# bleeding_edge-full_control.net
KiCad netlist of a schematic drawn in EasyEDA
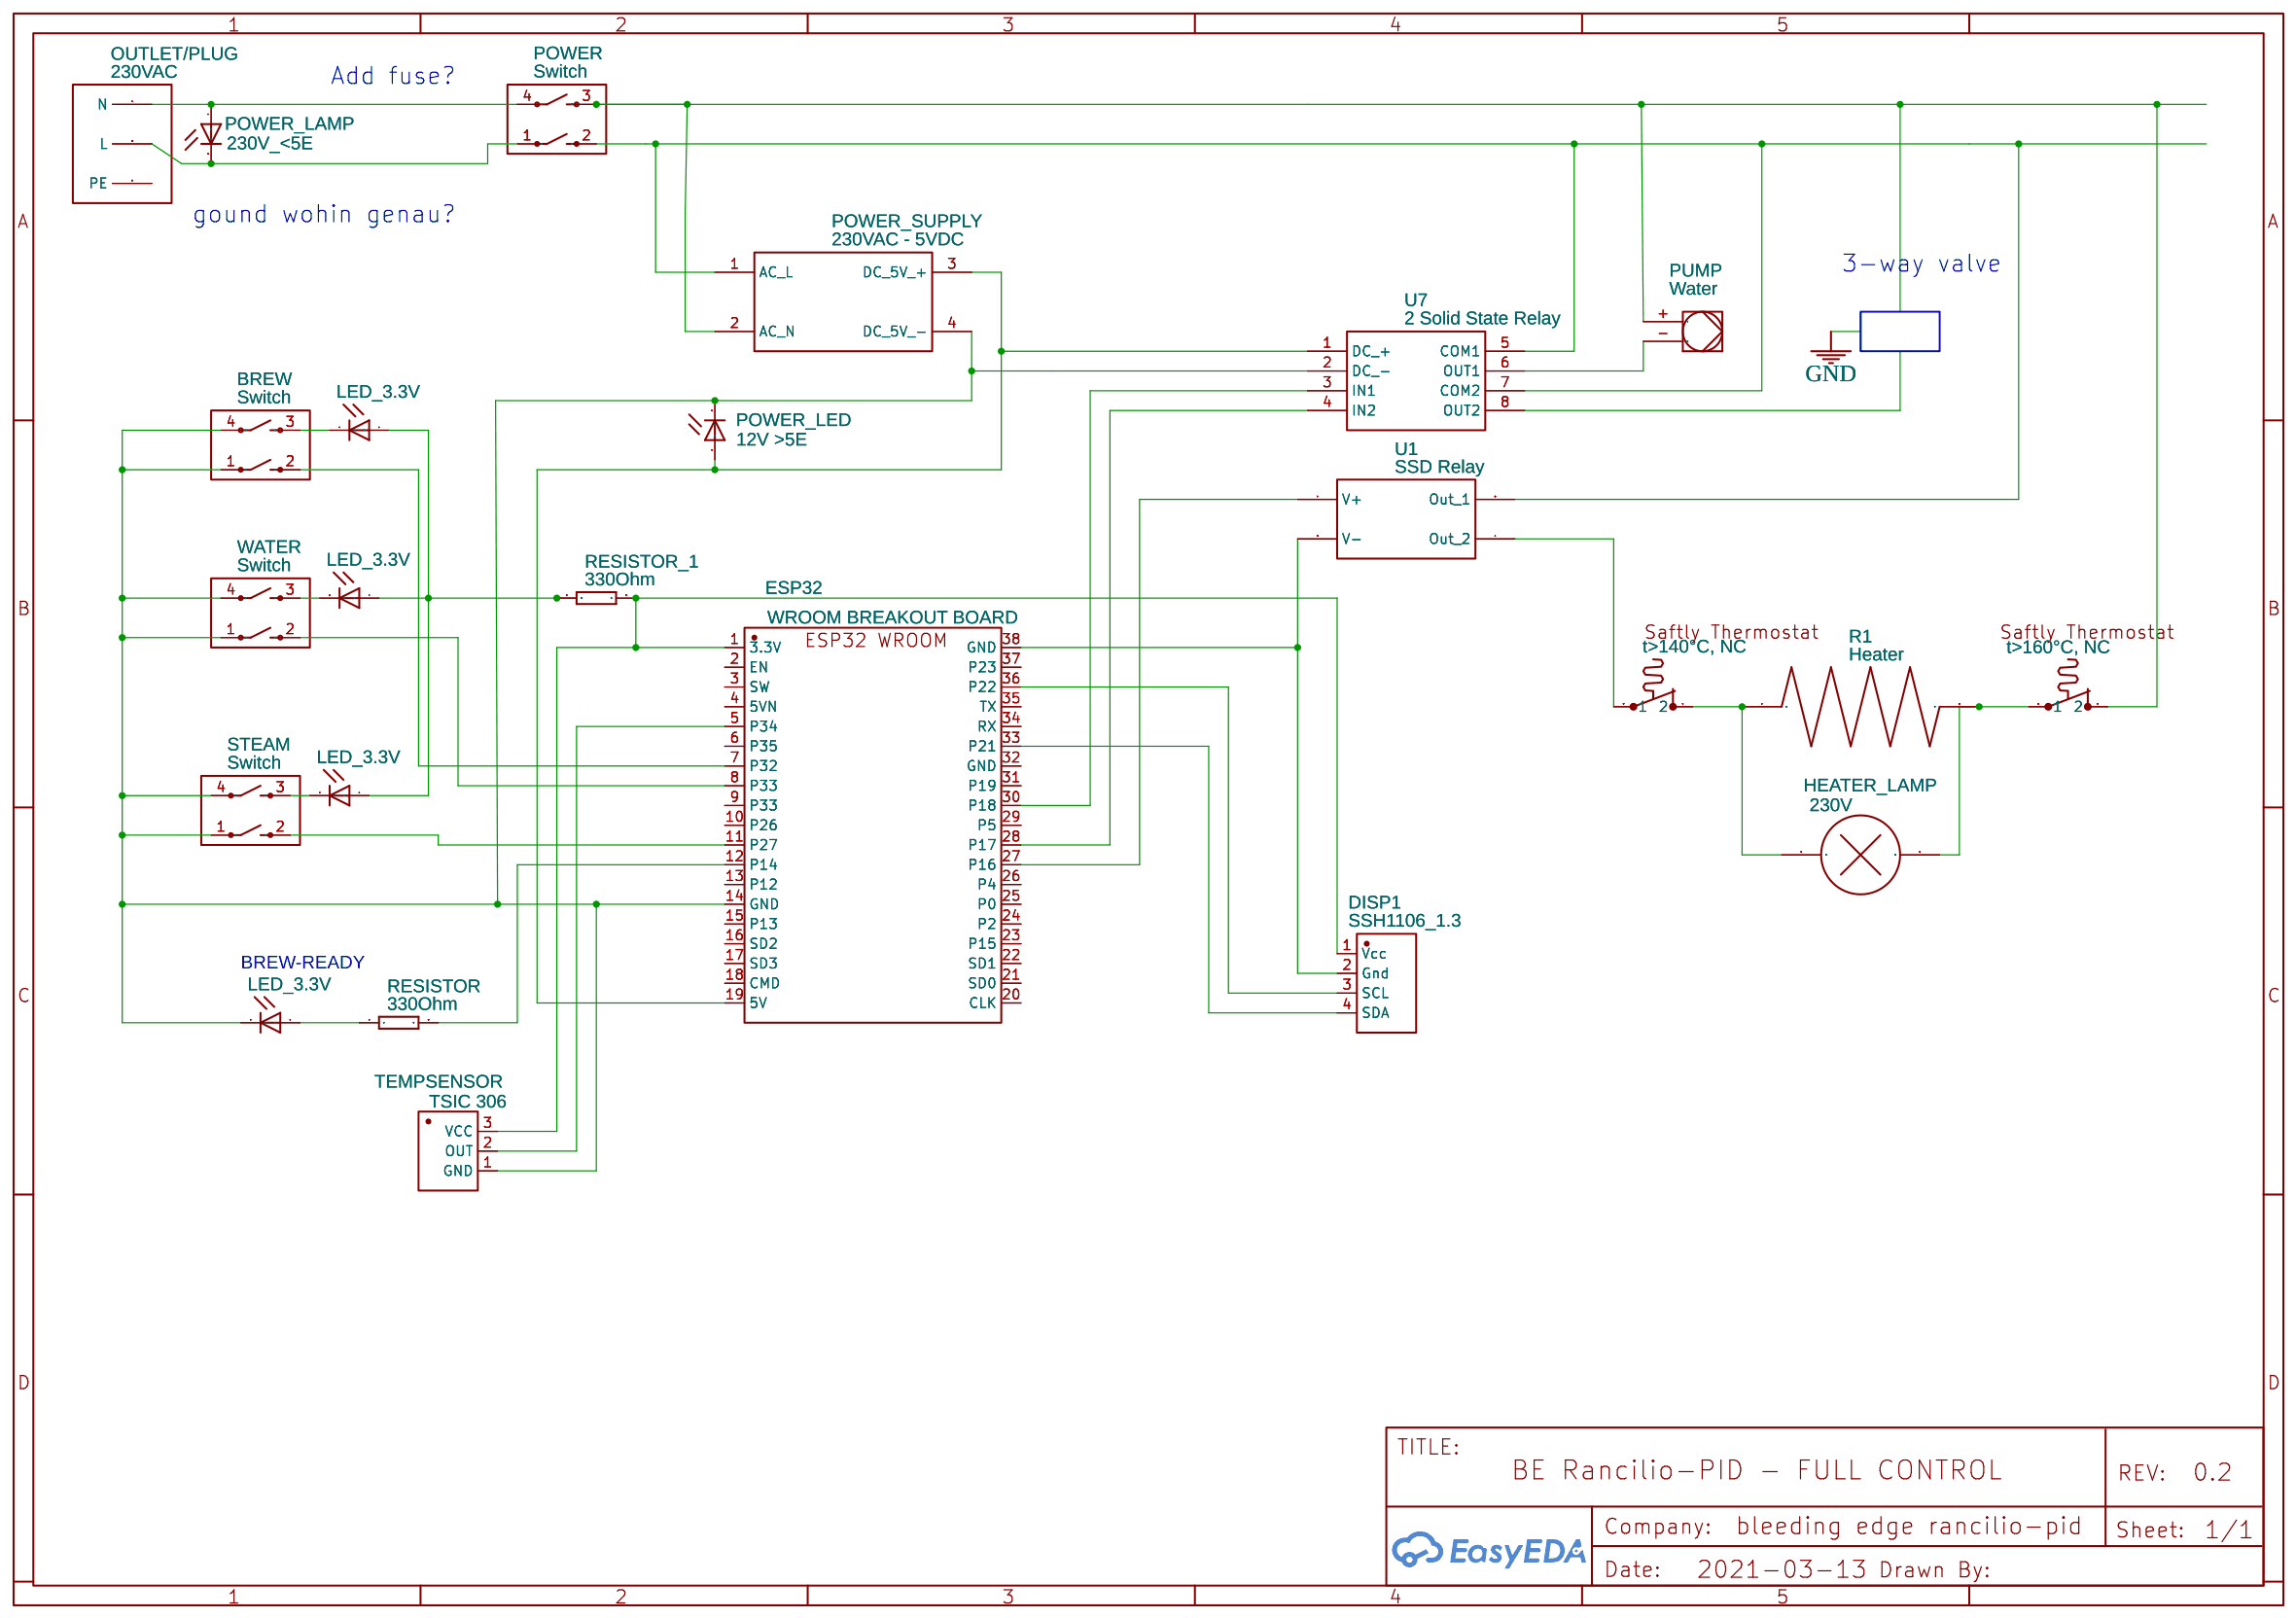
[diagram p0: schematic sheet]

(export (version "E")
  (design (tool "Eeschema 10.0.6"))
  (components
    (comp (ref "BREW")
      (value "Switch")
      (fields
        (field (name "BOM_Manufacturer Part") "Rancilio Switch")
        (field (name "BOM_Supplier Part") "C14121")
      )
      (libsource (lib "") (part "Rancilio Switch_1"))
    )
    (comp (ref "DISP1")
      (value "SSH1106_1.3")
      (fields (field (name "BOM_Manufacturer Part") "Tribium"))
      (libsource (lib "") (part "SSH1106_1.3"))
    )
    (comp (ref "ESP32")
      (value "WROOM BREAKOUT BOARD")
      (libsource (lib "") (part "ESP32 WROOM BREAKOUT BOARD"))
    )
    (comp (ref "HEATER_LAMP")
      (value "230V")
      (fields (field (name "BOM_Manufacturer Part") "Light"))
      (libsource (lib "") (part "Light"))
    )
    (comp (ref "LED1") (value "LED_3.3V") (libsource (lib "") (part "LED")))
    (comp (ref "LED2") (value "LED_3.3V") (libsource (lib "") (part "LED")))
    (comp (ref "LED3") (value "LED_3.3V") (libsource (lib "") (part "LED")))
    (comp (ref "LED4") (value "LED_3.3V") (libsource (lib "") (part "LED")))
    (comp (ref "OUTLET/PLUG")
      (value "230VAC")
      (fields (field (name "BOM_Supplier Part") "undefined"))
      (libsource (lib "") (part "230VAC OUTLET/PLUG"))
    )
    (comp (ref "POWER")
      (value "Switch")
      (fields
        (field (name "BOM_Manufacturer Part") "Rancilio Switch")
        (field (name "BOM_Supplier Part") "C14121")
      )
      (libsource (lib "") (part "Rancilio Switch_3"))
    )
    (comp (ref "POWER_LAMP") (value "230V_<5E") (libsource (lib "") (part "LED_2")))
    (comp (ref "POWER_LED") (value "12V >5E") (libsource (lib "") (part "LED_1")))
    (comp (ref "POWER_SUPPLY") (value "230VAC - 5VDC") (libsource (lib "") (part "230VAC - 5VDC")))
    (comp (ref "PUMP") (value "Water") (libsource (lib "") (part "pump")))
    (comp (ref "R1") (value "Heater") (libsource (lib "") (part "Heater")))
    (comp (ref "RESISTOR") (value "330Ohm") (libsource (lib "") (part "RESISTOR_1")))
    (comp (ref "RESISTOR_1") (value "330Ohm") (libsource (lib "") (part "RESISTOR")))
    (comp (ref "STEAM")
      (value "Switch")
      (fields
        (field (name "BOM_Manufacturer Part") "Rancilio Switch")
        (field (name "BOM_Supplier Part") "C14121")
      )
      (libsource (lib "") (part "Rancilio Switch_2"))
    )
    (comp (ref "TEMPSENSOR")
      (value "TSIC 306")
      (fields (field (name "BOM_Manufacturer Part") "Innovative Sensor Technology"))
      (libsource (lib "") (part "TSIC506F"))
    )
    (comp (ref "U1") (value "SSD Relay") (libsource (lib "") (part "SSD Relay")))
    (comp (ref "U6")
      (value "t>140°C, NC")
      (fields (field (name "BOM_Manufacturer Part") "Thermostat"))
      (libsource (lib "") (part "termostat NC_1"))
    )
    (comp (ref "U7") (value "2 Solid State Relay") (libsource (lib "") (part "2 Solid State Relay")))
    (comp (ref "U11")
      (value "t>160°C, NC")
      (fields (field (name "BOM_Manufacturer Part") "Thermostat"))
      (libsource (lib "") (part "termostat NC"))
    )
    (comp (ref "WATER")
      (value "Switch")
      (fields
        (field (name "BOM_Manufacturer Part") "Rancilio Switch")
        (field (name "BOM_Supplier Part") "C14121")
      )
      (libsource (lib "") (part "Rancilio Switch"))
    )
  )
  (nets
    (net (code "2") (name "Net-(DISP1-Gnd)") (class "Default")
      (node (ref "DISP1") (pin "2") (pinfunction "Gnd_2") (pintype "unspecified"))
      (node (ref "ESP32") (pin "38") (pinfunction "GND_38") (pintype "unspecified"))
      (node (ref "U1") (pin "2") (pinfunction "V-_2") (pintype "unspecified"))
    )
    (net (code "3") (name "Net-(DISP1-SCL)") (class "Default")
      (node (ref "DISP1") (pin "3") (pinfunction "SCL_3") (pintype "unspecified"))
      (node (ref "ESP32") (pin "36") (pinfunction "P22_36") (pintype "unspecified"))
    )
    (net (code "4") (name "Net-(DISP1-SDA)") (class "Default")
      (node (ref "DISP1") (pin "4") (pinfunction "SDA_4") (pintype "unspecified"))
      (node (ref "ESP32") (pin "33") (pinfunction "P21_33") (pintype "unspecified"))
    )
    (net (code "5") (name "Net-(DISP1-Vcc)") (class "Default")
      (node (ref "DISP1") (pin "1") (pinfunction "Vcc_1") (pintype "unspecified"))
      (node (ref "ESP32") (pin "1") (pinfunction "3.3V_1") (pintype "unspecified"))
      (node (ref "RESISTOR_1") (pin "2") (pinfunction "2_2") (pintype "unspecified"))
      (node (ref "TEMPSENSOR") (pin "3") (pinfunction "VCC_3") (pintype "unspecified"))
    )
    (net (code "6") (name "Net-(ESP32-5V)") (class "Default")
      (node (ref "ESP32") (pin "19") (pinfunction "5V_19") (pintype "unspecified"))
      (node (ref "POWER_LED") (pin "A") (pinfunction "A_A") (pintype "unspecified"))
      (node (ref "POWER_SUPPLY") (pin "3") (pinfunction "DC_5V_+_3") (pintype "unspecified"))
      (node (ref "U7") (pin "1") (pinfunction "DC_+_1") (pintype "unspecified"))
    )
    (net (code "7") (name "Net-(ESP32-P14)") (class "Default")
      (node (ref "ESP32") (pin "12") (pinfunction "P14_12") (pintype "unspecified"))
      (node (ref "RESISTOR") (pin "2") (pinfunction "2_2") (pintype "unspecified"))
    )
    (net (code "8") (name "Net-(ESP32-P16)") (class "Default")
      (node (ref "ESP32") (pin "27") (pinfunction "P16_27") (pintype "unspecified"))
      (node (ref "U1") (pin "1") (pinfunction "V+_1") (pintype "unspecified"))
    )
    (net (code "9") (name "Net-(ESP32-P17)") (class "Default")
      (node (ref "ESP32") (pin "28") (pinfunction "P17_28") (pintype "unspecified"))
      (node (ref "U7") (pin "4") (pinfunction "IN2_4") (pintype "unspecified"))
    )
    (net (code "10") (name "Net-(ESP32-P18)") (class "Default")
      (node (ref "ESP32") (pin "30") (pinfunction "P18_30") (pintype "unspecified"))
      (node (ref "U7") (pin "3") (pinfunction "IN1_3") (pintype "unspecified"))
    )
    (net (code "11") (name "Net-(ESP32-P27)") (class "Default")
      (node (ref "ESP32") (pin "11") (pinfunction "P27_11") (pintype "unspecified"))
      (node (ref "STEAM") (pin "2") (pinfunction "2_2") (pintype "unspecified"))
    )
    (net (code "12") (name "Net-(ESP32-P32)") (class "Default")
      (node (ref "BREW") (pin "2") (pinfunction "2_2") (pintype "unspecified"))
      (node (ref "ESP32") (pin "7") (pinfunction "P32_7") (pintype "unspecified"))
    )
    (net (code "13") (name "Net-(ESP32-P33-Pad8)") (class "Default")
      (node (ref "ESP32") (pin "8") (pinfunction "P33_8") (pintype "unspecified"))
      (node (ref "WATER") (pin "2") (pinfunction "2_2") (pintype "unspecified"))
    )
    (net (code "14") (name "Net-(ESP32-P34)") (class "Default")
      (node (ref "ESP32") (pin "5") (pinfunction "P34_5") (pintype "unspecified"))
      (node (ref "TEMPSENSOR") (pin "2") (pinfunction "OUT_2") (pintype "unspecified"))
    )
    (net (code "15") (name "Net-(LED1-C)") (class "Default")
      (node (ref "BREW") (pin "1") (pinfunction "1_1") (pintype "unspecified"))
      (node (ref "BREW") (pin "4") (pinfunction "4_4") (pintype "unspecified"))
      (node (ref "ESP32") (pin "14") (pinfunction "GND_14") (pintype "unspecified"))
      (node (ref "LED1") (pin "K") (pinfunction "C_K") (pintype "unspecified"))
      (node (ref "POWER_LED") (pin "K") (pinfunction "C_K") (pintype "unspecified"))
      (node (ref "POWER_SUPPLY") (pin "4") (pinfunction "DC_5V_-_4") (pintype "unspecified"))
      (node (ref "STEAM") (pin "1") (pinfunction "1_1") (pintype "unspecified"))
      (node (ref "STEAM") (pin "4") (pinfunction "4_4") (pintype "unspecified"))
      (node (ref "TEMPSENSOR") (pin "1") (pinfunction "GND_1") (pintype "unspecified"))
      (node (ref "U7") (pin "2") (pinfunction "DC_-_2") (pintype "unspecified"))
      (node (ref "WATER") (pin "1") (pinfunction "1_1") (pintype "unspecified"))
      (node (ref "WATER") (pin "4") (pinfunction "4_4") (pintype "unspecified"))
    )
    (net (code "16") (name "Net-(LED1-PadA)") (class "Default")
      (node (ref "LED1") (pin "A") (pinfunction "A_A") (pintype "unspecified"))
      (node (ref "RESISTOR") (pin "1") (pinfunction "1_1") (pintype "unspecified"))
    )
    (net (code "17") (name "Net-(LED2-C)") (class "Default")
      (node (ref "BREW") (pin "3") (pinfunction "3_3") (pintype "unspecified"))
      (node (ref "LED2") (pin "K") (pinfunction "C_K") (pintype "unspecified"))
    )
    (net (code "18") (name "Net-(LED2-PadA)") (class "Default")
      (node (ref "LED2") (pin "A") (pinfunction "A_A") (pintype "unspecified"))
      (node (ref "LED3") (pin "A") (pinfunction "A_A") (pintype "unspecified"))
      (node (ref "LED4") (pin "A") (pinfunction "A_A") (pintype "unspecified"))
      (node (ref "RESISTOR_1") (pin "1") (pinfunction "1_1") (pintype "unspecified"))
    )
    (net (code "19") (name "Net-(LED3-C)") (class "Default")
      (node (ref "LED3") (pin "K") (pinfunction "C_K") (pintype "unspecified"))
      (node (ref "WATER") (pin "3") (pinfunction "3_3") (pintype "unspecified"))
    )
    (net (code "20") (name "Net-(LED4-C)") (class "Default")
      (node (ref "LED4") (pin "K") (pinfunction "C_K") (pintype "unspecified"))
      (node (ref "STEAM") (pin "3") (pinfunction "3_3") (pintype "unspecified"))
    )
    (net (code "21") (name "Net-(OUTLET/PLUG-L)") (class "Default")
      (node (ref "OUTLET/PLUG") (pin "2") (pinfunction "L_2") (pintype "unspecified"))
      (node (ref "POWER") (pin "1") (pinfunction "1_1") (pintype "unspecified"))
      (node (ref "POWER_LAMP") (pin "K") (pinfunction "C_K") (pintype "unspecified"))
    )
    (net (code "22") (name "Net-(OUTLET/PLUG-N)") (class "Default")
      (node (ref "OUTLET/PLUG") (pin "1") (pinfunction "N_1") (pintype "unspecified"))
      (node (ref "POWER") (pin "4") (pinfunction "4_4") (pintype "unspecified"))
      (node (ref "POWER_LAMP") (pin "A") (pinfunction "A_A") (pintype "unspecified"))
    )
    (net (code "23") (name "Net-(POWER_SUPPLY-AC_L)") (class "Default")
      (node (ref "POWER") (pin "2") (pinfunction "2_2") (pintype "unspecified"))
      (node (ref "POWER_SUPPLY") (pin "1") (pinfunction "AC_L_1") (pintype "unspecified"))
      (node (ref "U1") (pin "3") (pinfunction "Out_1_3") (pintype "unspecified"))
      (node (ref "U7") (pin "5") (pinfunction "COM1_5") (pintype "unspecified"))
      (node (ref "U7") (pin "7") (pinfunction "COM2_7") (pintype "unspecified"))
    )
    (net (code "24") (name "Net-(POWER_SUPPLY-AC_N)") (class "Default")
      (node (ref "POWER") (pin "3") (pinfunction "3_3") (pintype "unspecified"))
      (node (ref "POWER_SUPPLY") (pin "2") (pinfunction "AC_N_2") (pintype "unspecified"))
      (node (ref "PUMP") (pin "+") (pinfunction "1_+") (pintype "unspecified"))
      (node (ref "U11") (pin "1") (pinfunction "2_1") (pintype "unspecified"))
    )
    (net (code "25") (name "Net-(PUMP-2)") (class "Default")
      (node (ref "PUMP") (pin "-") (pinfunction "2_-") (pintype "unspecified"))
      (node (ref "U7") (pin "6") (pinfunction "OUT1_6") (pintype "unspecified"))
    )
    (net (code "26") (name "Net-(U1-Out_2)") (class "Default")
      (node (ref "U1") (pin "4") (pinfunction "Out_2_4") (pintype "unspecified"))
      (node (ref "U6") (pin "2") (pinfunction "1_2") (pintype "unspecified"))
    )
    (net (code "27") (name "Net-(U6-2)") (class "Default")
      (node (ref "HEATER_LAMP") (pin "2") (pinfunction "2_2") (pintype "unspecified"))
      (node (ref "R1") (pin "1") (pinfunction "1_1") (pintype "bidirectional"))
      (node (ref "U6") (pin "1") (pinfunction "2_1") (pintype "unspecified"))
    )
    (net (code "28") (name "Net-(U11-1)") (class "Default")
      (node (ref "HEATER_LAMP") (pin "1") (pinfunction "1_1") (pintype "unspecified"))
      (node (ref "R1") (pin "2") (pinfunction "2_2") (pintype "bidirectional"))
      (node (ref "U11") (pin "2") (pinfunction "1_2") (pintype "unspecified"))
    )
    (net (code "29") (name "unconnected-(ESP32-5VN-Pad4)") (class "Default")
      (node (ref "ESP32") (pin "4") (pinfunction "5VN_4") (pintype "unspecified"))
    )
    (net (code "30") (name "unconnected-(ESP32-CLK-Pad20)") (class "Default")
      (node (ref "ESP32") (pin "20") (pinfunction "CLK_20") (pintype "unspecified"))
    )
    (net (code "31") (name "unconnected-(ESP32-CMD-Pad18)") (class "Default")
      (node (ref "ESP32") (pin "18") (pinfunction "CMD_18") (pintype "unspecified"))
    )
    (net (code "32") (name "unconnected-(ESP32-EN-Pad2)") (class "Default")
      (node (ref "ESP32") (pin "2") (pinfunction "EN_2") (pintype "unspecified"))
    )
    (net (code "33") (name "unconnected-(ESP32-GND-Pad32)") (class "Default")
      (node (ref "ESP32") (pin "32") (pinfunction "GND_32") (pintype "unspecified"))
    )
    (net (code "34") (name "unconnected-(ESP32-P0-Pad25)") (class "Default")
      (node (ref "ESP32") (pin "25") (pinfunction "P0_25") (pintype "unspecified"))
    )
    (net (code "35") (name "unconnected-(ESP32-P2-Pad24)") (class "Default")
      (node (ref "ESP32") (pin "24") (pinfunction "P2_24") (pintype "unspecified"))
    )
    (net (code "36") (name "unconnected-(ESP32-P4-Pad26)") (class "Default")
      (node (ref "ESP32") (pin "26") (pinfunction "P4_26") (pintype "unspecified"))
    )
    (net (code "37") (name "unconnected-(ESP32-P5-Pad29)") (class "Default")
      (node (ref "ESP32") (pin "29") (pinfunction "P5_29") (pintype "unspecified"))
    )
    (net (code "38") (name "unconnected-(ESP32-P12-Pad13)") (class "Default")
      (node (ref "ESP32") (pin "13") (pinfunction "P12_13") (pintype "unspecified"))
    )
    (net (code "39") (name "unconnected-(ESP32-P13-Pad15)") (class "Default")
      (node (ref "ESP32") (pin "15") (pinfunction "P13_15") (pintype "unspecified"))
    )
    (net (code "40") (name "unconnected-(ESP32-P15-Pad23)") (class "Default")
      (node (ref "ESP32") (pin "23") (pinfunction "P15_23") (pintype "unspecified"))
    )
    (net (code "41") (name "unconnected-(ESP32-P19-Pad31)") (class "Default")
      (node (ref "ESP32") (pin "31") (pinfunction "P19_31") (pintype "unspecified"))
    )
    (net (code "42") (name "unconnected-(ESP32-P23-Pad37)") (class "Default")
      (node (ref "ESP32") (pin "37") (pinfunction "P23_37") (pintype "unspecified"))
    )
    (net (code "43") (name "unconnected-(ESP32-P26-Pad10)") (class "Default")
      (node (ref "ESP32") (pin "10") (pinfunction "P26_10") (pintype "unspecified"))
    )
    (net (code "44") (name "unconnected-(ESP32-P33-Pad9)") (class "Default")
      (node (ref "ESP32") (pin "9") (pinfunction "P33_9") (pintype "unspecified"))
    )
    (net (code "45") (name "unconnected-(ESP32-P35-Pad6)") (class "Default")
      (node (ref "ESP32") (pin "6") (pinfunction "P35_6") (pintype "unspecified"))
    )
    (net (code "46") (name "unconnected-(ESP32-RX-Pad34)") (class "Default")
      (node (ref "ESP32") (pin "34") (pinfunction "RX_34") (pintype "unspecified"))
    )
    (net (code "47") (name "unconnected-(ESP32-SD0-Pad21)") (class "Default")
      (node (ref "ESP32") (pin "21") (pinfunction "SD0_21") (pintype "unspecified"))
    )
    (net (code "48") (name "unconnected-(ESP32-SD1-Pad22)") (class "Default")
      (node (ref "ESP32") (pin "22") (pinfunction "SD1_22") (pintype "unspecified"))
    )
    (net (code "49") (name "unconnected-(ESP32-SD2-Pad16)") (class "Default")
      (node (ref "ESP32") (pin "16") (pinfunction "SD2_16") (pintype "unspecified"))
    )
    (net (code "50") (name "unconnected-(ESP32-SD3-Pad17)") (class "Default")
      (node (ref "ESP32") (pin "17") (pinfunction "SD3_17") (pintype "unspecified"))
    )
    (net (code "51") (name "unconnected-(ESP32-SW-Pad3)") (class "Default")
      (node (ref "ESP32") (pin "3") (pinfunction "SW_3") (pintype "unspecified"))
    )
    (net (code "52") (name "unconnected-(ESP32-TX-Pad35)") (class "Default")
      (node (ref "ESP32") (pin "35") (pinfunction "TX_35") (pintype "unspecified"))
    )
    (net (code "53") (name "unconnected-(OUTLET/PLUG-PE-Pad3)") (class "Default")
      (node (ref "OUTLET/PLUG") (pin "3") (pinfunction "PE_3") (pintype "unspecified"))
    )
    (net (code "54") (name "unconnected-(U7-OUT2-Pad8)") (class "Default")
      (node (ref "U7") (pin "8") (pinfunction "OUT2_8") (pintype "unspecified"))
    )
  )
)
